# PowerSwitch_P3V3.net
KiCad netlist of a schematic drawn in Altium Designer
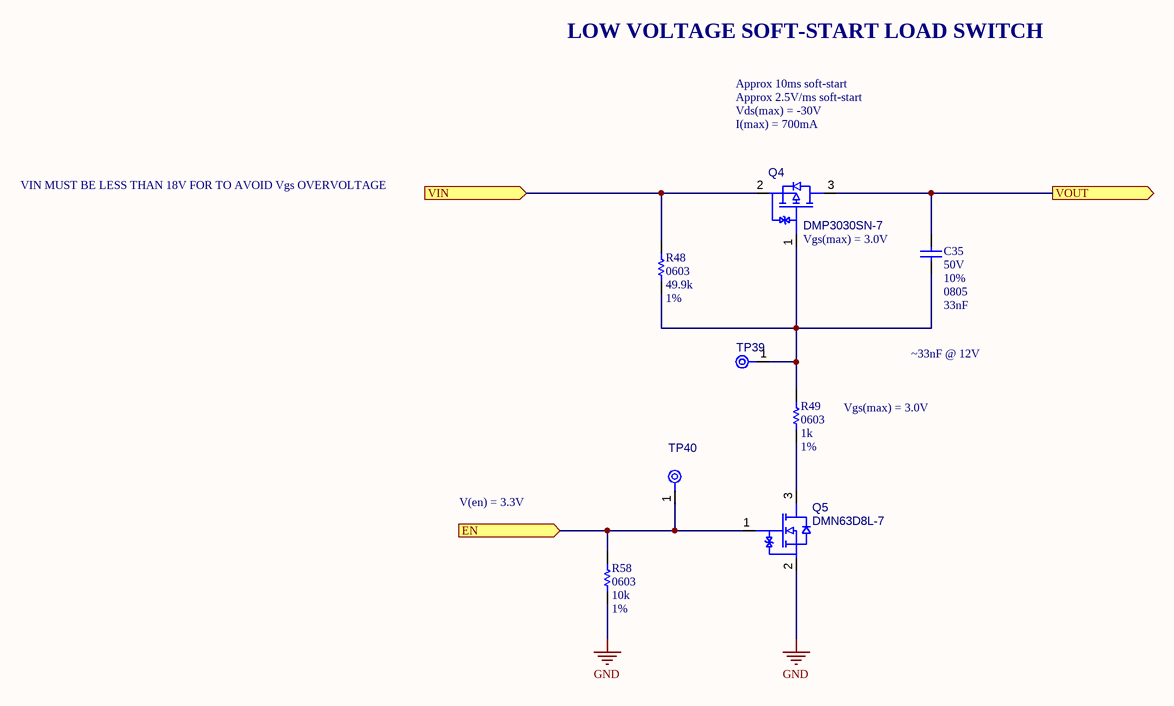
[diagram p0: PowerSwitch_P3V3.SchDoc]

(export (version "E")
  (design (tool "Eeschema 10.0.6"))
  (components
    (comp (ref "C35")
      (value "33nF")
      (footprint "CAPC2013X95X50ML10T25")
      (description "Chip Capacitor, 33nF, 10%, 50 V, X7R 0805 (2012 Metric)")
      (fields
        (field (name "VOLTAGE RATING") "50V")
        (field (name "TOLERANCE") "10%")
        (field (name "CASE/PACKAGE") "0805")
        (field (name "Comment") "Capacitor 33nF 10%, 50V, X7R, 0805")
      )
      (libsource (lib "Applied Physics Lab") (part "CAP-NP-2"))
    )
    (comp (ref "Q4")
      (value "DMP3030SN-7")
      (footprint "SOT95P164X140-3M")
      (description "Trans Mosfet P-ch 30V 0.7A 3-PIN SC-59 T/r / Mosfet P-ch 30V 700MA SC59-3")
      (libsource (lib "Applied Physics Lab") (part "CMP-00006-6"))
    )
    (comp (ref "Q5")
      (value "DMN63D8L-7")
      (footprint "SOT95P240X110-3M")
      (description "Trans Mosfet N-ch 30V 0.35A 3-PIN SOT-23 T/r")
      (libsource (lib "Applied Physics Lab") (part "CMP-00005-6"))
    )
    (comp (ref "R48")
      (value "49.9k")
      (footprint "RESC1608X55X25ML10T15")
      (description "Chip Resistor, 49.9k Ohm, +/- 1%, 0.1 W, -55 to 155 degC, 0603 (1608 Metric)")
      (fields
        (field (name "POWER") "100mW")
        (field (name "CASE/PACKAGE") "0603")
        (field (name "TOLERANCE") "1%")
        (field (name "Comment") "Resistor 49K9 +/-1% 0603 100 mW")
      )
      (libsource (lib "Applied Physics Lab") (part "RES-2"))
    )
    (comp (ref "R49")
      (value "1k")
      (footprint "RESC1608X55X25ML10T15")
      (description "Chip Resistor, 1 KOhm, +/-1%, 0.1 W, -55 to 155 degC, 0603 (1608 Metric)")
      (fields
        (field (name "POWER") "100mW")
        (field (name "CASE/PACKAGE") "0603")
        (field (name "TOLERANCE") "1%")
        (field (name "Comment") "Resistor 1k +/-1% 0603 100 mW")
      )
      (libsource (lib "Applied Physics Lab") (part "RES-2"))
    )
    (comp (ref "R58")
      (value "10k")
      (footprint "RESC1608X55X25ML10T15")
      (description "Chip Resistor, 10 KOhm, +/- 1%, 01 W, -55 to 155 degC, 0603 (1608 Metric)")
      (fields
        (field (name "POWER") "100mW")
        (field (name "CASE/PACKAGE") "0603")
        (field (name "TOLERANCE") "1%")
        (field (name "Comment") "Resistor 10k +/-1% 0603 100 mW")
      )
      (libsource (lib "Applied Physics Lab") (part "RES-2"))
    )
    (comp (ref "TP39")
      (value "TPAD6R-CIRCLED")
      (footprint "TP06R - Circled")
      (description "0.6mm round with a silkscreen circle.")
      (libsource (lib "Applied Physics Lab") (part "CMP-001-0001-4"))
    )
    (comp (ref "TP40")
      (value "TPAD6R-CIRCLED")
      (footprint "TP06R - Circled")
      (description "0.6mm round with a silkscreen circle.")
      (libsource (lib "Applied Physics Lab") (part "CMP-001-0001-4"))
    )
  )
  (nets
    (net (code "1") (name "/EN") (class "Default")
      (node (ref "Q5") (pin "1") (pinfunction "G_1") (pintype "passive"))
      (node (ref "R58") (pin "2") (pinfunction "2_2") (pintype "passive"))
      (node (ref "TP40") (pin "1") (pinfunction "TP_1") (pintype "passive"))
    )
    (net (code "2") (name "/VIN") (class "Default")
      (node (ref "Q4") (pin "2") (pinfunction "S_2") (pintype "passive"))
      (node (ref "R48") (pin "2") (pinfunction "2_2") (pintype "passive"))
    )
    (net (code "3") (name "/VOUT") (class "Default")
      (node (ref "C35") (pin "2") (pinfunction "2_2") (pintype "passive"))
      (node (ref "Q4") (pin "3") (pinfunction "D_3") (pintype "passive"))
    )
    (net (code "4") (name "GND") (class "Default")
      (node (ref "Q5") (pin "2") (pinfunction "S_2") (pintype "passive"))
      (node (ref "R58") (pin "1") (pinfunction "1_1") (pintype "passive"))
    )
    (net (code "5") (name "Net-(Q4-G)") (class "Default")
      (node (ref "C35") (pin "1") (pinfunction "1_1") (pintype "passive"))
      (node (ref "Q4") (pin "1") (pinfunction "G_1") (pintype "passive"))
      (node (ref "R48") (pin "1") (pinfunction "1_1") (pintype "passive"))
      (node (ref "R49") (pin "2") (pinfunction "2_2") (pintype "passive"))
      (node (ref "TP39") (pin "1") (pinfunction "TP_1") (pintype "passive"))
    )
    (net (code "6") (name "Net-(Q5-D)") (class "Default")
      (node (ref "Q5") (pin "3") (pinfunction "D_3") (pintype "passive"))
      (node (ref "R49") (pin "1") (pinfunction "1_1") (pintype "passive"))
    )
  )
)
